# air_quality.net
KiCad netlist of a schematic drawn in EAGLE
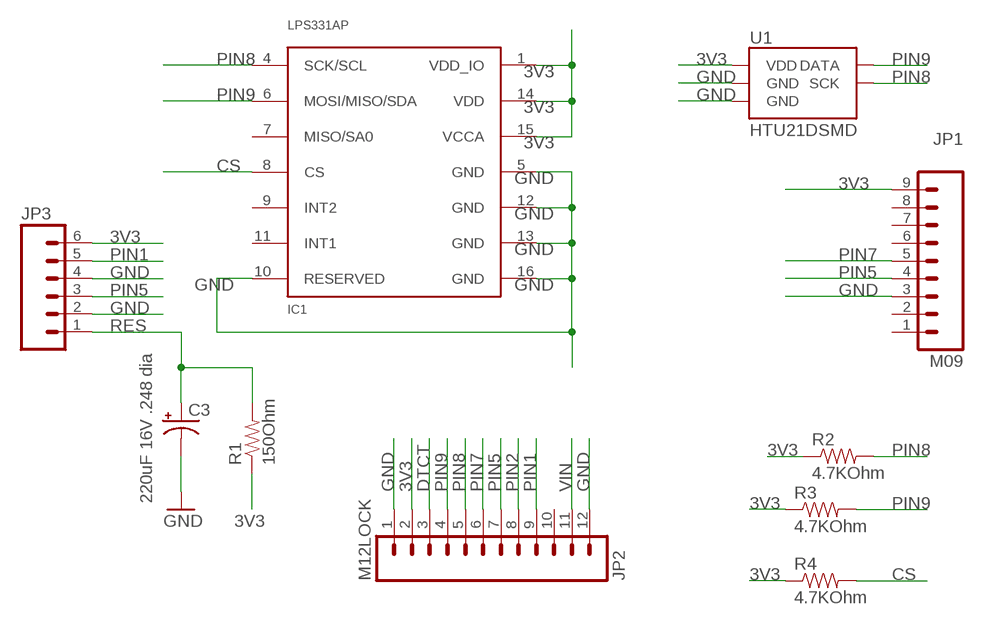
[diagram p0: schematic, sheet 1]

(export (version "E")
  (design (tool "Eeschema 10.0.6"))
  (components
    (comp (ref "C3")
      (value "220uF 16V .248 dia")
      (footprint "eagle-import:153CLV-0605")
      (libsource (lib "eagle-import") (part "CPOL-US153CLV-0605"))
    )
    (comp (ref "IC1")
      (value "LPS331AP")
      (footprint "eagle-import:HCLGA-16L")
      (libsource (lib "eagle-import") (part "LPS331AP"))
    )
    (comp (ref "JP1")
      (value "M09")
      (footprint "eagle-import:1X09")
      (libsource (lib "eagle-import") (part "M09"))
    )
    (comp (ref "JP2")
      (value "M12LOCK")
      (footprint "eagle-import:1X12_LOCK")
      (libsource (lib "eagle-import") (part "M12LOCK"))
    )
    (comp (ref "JP3")
      (value "M06LOCK")
      (footprint "eagle-import:1X06_LOCK")
      (libsource (lib "eagle-import") (part "M06LOCK"))
    )
    (comp (ref "R1")
      (value "150Ohm")
      (footprint "eagle-import:0402-RES")
      (libsource (lib "eagle-import") (part "RESISTOR0402-RES"))
    )
    (comp (ref "R2")
      (value "4.7KOhm")
      (footprint "eagle-import:0402-RES")
      (libsource (lib "eagle-import") (part "RESISTOR0402-RES"))
    )
    (comp (ref "R3")
      (value "4.7KOhm")
      (footprint "eagle-import:0402-RES")
      (libsource (lib "eagle-import") (part "RESISTOR0402-RES"))
    )
    (comp (ref "R4")
      (value "4.7KOhm")
      (footprint "eagle-import:0402-RES")
      (libsource (lib "eagle-import") (part "RESISTOR0402-RES"))
    )
    (comp (ref "U1")
      (value "HTU21DSMD")
      (footprint "eagle-import:HTU21D")
      (libsource (lib "eagle-import") (part "HTU21DSMD"))
    )
  )
  (nets
    (net (code "1") (name "/3V3") (class "Default")
      (node (ref "IC1") (pin "1") (pinfunction "VDD_IO_1") (pintype "power_in"))
      (node (ref "IC1") (pin "14") (pinfunction "VDD_14") (pintype "power_in"))
      (node (ref "IC1") (pin "15") (pinfunction "VCCA_15") (pintype "power_in"))
      (node (ref "JP1") (pin "9") (pinfunction "9_9") (pintype "passive"))
      (node (ref "JP2") (pin "2") (pinfunction "2_2") (pintype "passive"))
      (node (ref "JP3") (pin "6") (pinfunction "6_6") (pintype "passive"))
      (node (ref "R1") (pin "1") (pinfunction "1_1") (pintype "passive"))
      (node (ref "R2") (pin "1") (pinfunction "1_1") (pintype "passive"))
      (node (ref "R3") (pin "1") (pinfunction "1_1") (pintype "passive"))
      (node (ref "R4") (pin "1") (pinfunction "1_1") (pintype "passive"))
      (node (ref "U1") (pin "VDD") (pinfunction "VDD_VDD") (pintype "power_in"))
    )
    (net (code "2") (name "/CS") (class "Default")
      (node (ref "IC1") (pin "8") (pinfunction "CS_8") (pintype "input"))
      (node (ref "R4") (pin "2") (pinfunction "2_2") (pintype "passive"))
    )
    (net (code "3") (name "/DTCT") (class "Default")
      (node (ref "JP2") (pin "3") (pinfunction "3_3") (pintype "passive"))
    )
    (net (code "4") (name "/PIN1") (class "Default")
      (node (ref "JP2") (pin "9") (pinfunction "9_9") (pintype "passive"))
      (node (ref "JP3") (pin "5") (pinfunction "5_5") (pintype "passive"))
    )
    (net (code "5") (name "/PIN2") (class "Default")
      (node (ref "JP2") (pin "8") (pinfunction "8_8") (pintype "passive"))
    )
    (net (code "6") (name "/PIN5") (class "Default")
      (node (ref "JP1") (pin "4") (pinfunction "4_4") (pintype "passive"))
      (node (ref "JP2") (pin "7") (pinfunction "7_7") (pintype "passive"))
      (node (ref "JP3") (pin "3") (pinfunction "3_3") (pintype "passive"))
    )
    (net (code "7") (name "/PIN7") (class "Default")
      (node (ref "JP1") (pin "5") (pinfunction "5_5") (pintype "passive"))
      (node (ref "JP2") (pin "6") (pinfunction "6_6") (pintype "passive"))
    )
    (net (code "8") (name "/PIN8") (class "Default")
      (node (ref "IC1") (pin "4") (pinfunction "SCK/SCL_4") (pintype "input"))
      (node (ref "JP2") (pin "5") (pinfunction "5_5") (pintype "passive"))
      (node (ref "R2") (pin "2") (pinfunction "2_2") (pintype "passive"))
      (node (ref "U1") (pin "SCK") (pinfunction "SCK_SCK") (pintype "input"))
    )
    (net (code "9") (name "/PIN9") (class "Default")
      (node (ref "IC1") (pin "6") (pinfunction "MOSI/MISO/SDA_6") (pintype "bidirectional"))
      (node (ref "JP2") (pin "4") (pinfunction "4_4") (pintype "passive"))
      (node (ref "R3") (pin "2") (pinfunction "2_2") (pintype "passive"))
      (node (ref "U1") (pin "DATA") (pinfunction "DATA_DATA") (pintype "bidirectional"))
    )
    (net (code "10") (name "/RES") (class "Default")
      (node (ref "C3") (pin "+") (pinfunction "+_+") (pintype "passive"))
      (node (ref "JP3") (pin "1") (pinfunction "1_1") (pintype "passive"))
      (node (ref "R1") (pin "2") (pinfunction "2_2") (pintype "passive"))
    )
    (net (code "11") (name "/VIN") (class "Default")
      (node (ref "JP2") (pin "11") (pinfunction "11_11") (pintype "passive"))
    )
    (net (code "12") (name "GND") (class "Default")
      (node (ref "C3") (pin "-") (pinfunction "-_-") (pintype "passive"))
      (node (ref "IC1") (pin "10") (pinfunction "RESERVED_10") (pintype "input"))
      (node (ref "IC1") (pin "12") (pinfunction "GND_12") (pintype "power_in"))
      (node (ref "IC1") (pin "13") (pinfunction "GND_13") (pintype "power_in"))
      (node (ref "IC1") (pin "16") (pinfunction "GND_16") (pintype "power_in"))
      (node (ref "IC1") (pin "5") (pinfunction "GND_5") (pintype "power_in"))
      (node (ref "JP1") (pin "3") (pinfunction "3_3") (pintype "passive"))
      (node (ref "JP2") (pin "1") (pinfunction "1_1") (pintype "passive"))
      (node (ref "JP2") (pin "12") (pinfunction "12_12") (pintype "passive"))
      (node (ref "JP3") (pin "2") (pinfunction "2_2") (pintype "passive"))
      (node (ref "JP3") (pin "4") (pinfunction "4_4") (pintype "passive"))
      (node (ref "U1") (pin "7") (pinfunction "GND_7") (pintype "power_in"))
      (node (ref "U1") (pin "GND") (pinfunction "GND_GND") (pintype "power_in"))
    )
    (net (code "13") (name "unconnected-(IC1-INT1-Pad11)") (class "Default")
      (node (ref "IC1") (pin "11") (pinfunction "INT1_11") (pintype "output"))
    )
    (net (code "14") (name "unconnected-(IC1-INT2-Pad9)") (class "Default")
      (node (ref "IC1") (pin "9") (pinfunction "INT2_9") (pintype "output"))
    )
    (net (code "15") (name "unconnected-(IC1-MISO{slash}SA0-Pad7)") (class "Default")
      (node (ref "IC1") (pin "7") (pinfunction "MISO/SA0_7") (pintype "output"))
    )
    (net (code "16") (name "unconnected-(JP1-Pad1)") (class "Default")
      (node (ref "JP1") (pin "1") (pinfunction "1_1") (pintype "passive"))
    )
    (net (code "17") (name "unconnected-(JP1-Pad2)") (class "Default")
      (node (ref "JP1") (pin "2") (pinfunction "2_2") (pintype "passive"))
    )
    (net (code "18") (name "unconnected-(JP1-Pad6)") (class "Default")
      (node (ref "JP1") (pin "6") (pinfunction "6_6") (pintype "passive"))
    )
    (net (code "19") (name "unconnected-(JP1-Pad7)") (class "Default")
      (node (ref "JP1") (pin "7") (pinfunction "7_7") (pintype "passive"))
    )
    (net (code "20") (name "unconnected-(JP1-Pad8)") (class "Default")
      (node (ref "JP1") (pin "8") (pinfunction "8_8") (pintype "passive"))
    )
    (net (code "21") (name "unconnected-(JP2-Pad10)") (class "Default")
      (node (ref "JP2") (pin "10") (pinfunction "10_10") (pintype "passive"))
    )
  )
)
